# grbl2prll.net
KiCad netlist of a schematic drawn in EAGLE
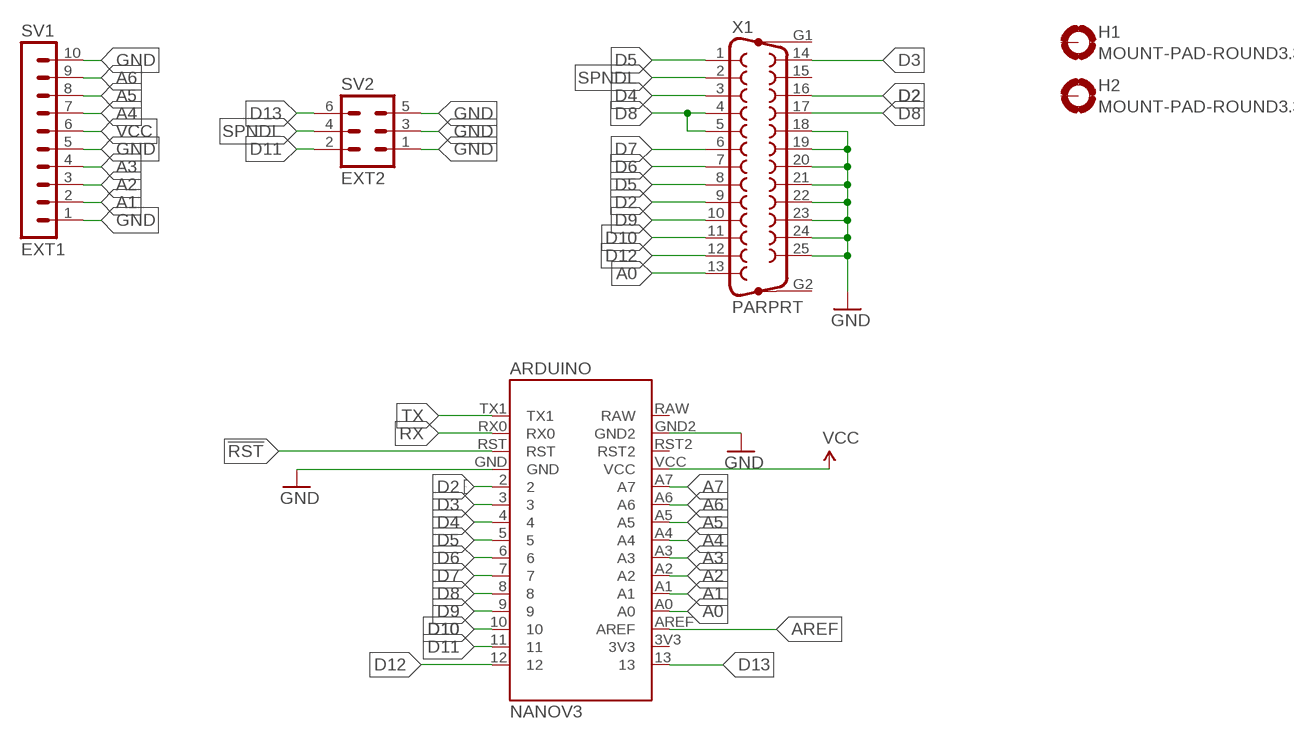
[diagram p0: schematic, sheet 1]

(export (version "E")
  (design (tool "Eeschema 10.0.6"))
  (components
    (comp (ref "ARDUINO")
      (value "NANOV3")
      (footprint "eagle-import:NANOV3")
      (libsource (lib "eagle-import") (part "NANOV3"))
    )
    (comp (ref "H1")
      (value "MOUNT-PAD-ROUND3.3")
      (footprint "eagle-import:3,3-PAD")
      (libsource (lib "eagle-import") (part "MOUNT-PAD-ROUND3.3"))
    )
    (comp (ref "H2")
      (value "MOUNT-PAD-ROUND3.3")
      (footprint "eagle-import:3,3-PAD")
      (libsource (lib "eagle-import") (part "MOUNT-PAD-ROUND3.3"))
    )
    (comp (ref "SV1")
      (value "EXT1")
      (footprint "eagle-import:MA10-1")
      (libsource (lib "eagle-import") (part "MA10-1"))
    )
    (comp (ref "SV2")
      (value "EXT2")
      (footprint "eagle-import:MA03-2")
      (libsource (lib "eagle-import") (part "MA03-2"))
    )
    (comp (ref "X1")
      (value "PARPRT")
      (footprint "eagle-import:F25HP")
      (libsource (lib "eagle-import") (part "F25HP"))
    )
  )
  (nets
    (net (code "1") (name "/~{RST}") (class "Default")
      (node (ref "ARDUINO") (pin "RST") (pinfunction "RST_RST") (pintype "bidirectional"))
    )
    (net (code "2") (name "A0") (class "Default")
      (node (ref "ARDUINO") (pin "A0") (pinfunction "A0_A0") (pintype "bidirectional"))
      (node (ref "X1") (pin "13") (pinfunction "13_13") (pintype "passive"))
    )
    (net (code "3") (name "A1") (class "Default")
      (node (ref "ARDUINO") (pin "A1") (pinfunction "A1_A1") (pintype "bidirectional"))
      (node (ref "SV1") (pin "2") (pinfunction "2_2") (pintype "passive"))
    )
    (net (code "4") (name "A2") (class "Default")
      (node (ref "ARDUINO") (pin "A2") (pinfunction "A2_A2") (pintype "bidirectional"))
      (node (ref "SV1") (pin "3") (pinfunction "3_3") (pintype "passive"))
    )
    (net (code "5") (name "A3") (class "Default")
      (node (ref "ARDUINO") (pin "A3") (pinfunction "A3_A3") (pintype "bidirectional"))
      (node (ref "SV1") (pin "4") (pinfunction "4_4") (pintype "passive"))
    )
    (net (code "6") (name "A4") (class "Default")
      (node (ref "ARDUINO") (pin "A4") (pinfunction "A4_A4") (pintype "bidirectional"))
      (node (ref "SV1") (pin "7") (pinfunction "7_7") (pintype "passive"))
    )
    (net (code "7") (name "A5") (class "Default")
      (node (ref "ARDUINO") (pin "A5") (pinfunction "A5_A5") (pintype "bidirectional"))
      (node (ref "SV1") (pin "8") (pinfunction "8_8") (pintype "passive"))
    )
    (net (code "8") (name "A6") (class "Default")
      (node (ref "ARDUINO") (pin "A6") (pinfunction "A6_A6") (pintype "bidirectional"))
      (node (ref "SV1") (pin "9") (pinfunction "9_9") (pintype "passive"))
    )
    (net (code "9") (name "A7") (class "Default")
      (node (ref "ARDUINO") (pin "A7") (pinfunction "A7_A7") (pintype "bidirectional"))
    )
    (net (code "10") (name "AREF") (class "Default")
      (node (ref "ARDUINO") (pin "AREF") (pinfunction "AREF_AREF") (pintype "bidirectional"))
    )
    (net (code "11") (name "D2") (class "Default")
      (node (ref "ARDUINO") (pin "2") (pinfunction "2_2") (pintype "bidirectional"))
      (node (ref "X1") (pin "16") (pinfunction "16_16") (pintype "passive"))
      (node (ref "X1") (pin "9") (pinfunction "9_9") (pintype "passive"))
    )
    (net (code "12") (name "D3") (class "Default")
      (node (ref "ARDUINO") (pin "3") (pinfunction "3_3") (pintype "bidirectional"))
      (node (ref "X1") (pin "14") (pinfunction "14_14") (pintype "passive"))
    )
    (net (code "13") (name "D4") (class "Default")
      (node (ref "ARDUINO") (pin "4") (pinfunction "4_4") (pintype "bidirectional"))
      (node (ref "X1") (pin "3") (pinfunction "3_3") (pintype "passive"))
    )
    (net (code "14") (name "D5") (class "Default")
      (node (ref "ARDUINO") (pin "5") (pinfunction "5_5") (pintype "bidirectional"))
      (node (ref "X1") (pin "1") (pinfunction "1_1") (pintype "passive"))
      (node (ref "X1") (pin "8") (pinfunction "8_8") (pintype "passive"))
    )
    (net (code "15") (name "D6") (class "Default")
      (node (ref "ARDUINO") (pin "6") (pinfunction "6_6") (pintype "bidirectional"))
      (node (ref "X1") (pin "7") (pinfunction "7_7") (pintype "passive"))
    )
    (net (code "16") (name "D7") (class "Default")
      (node (ref "ARDUINO") (pin "7") (pinfunction "7_7") (pintype "bidirectional"))
      (node (ref "X1") (pin "6") (pinfunction "6_6") (pintype "passive"))
    )
    (net (code "17") (name "D8") (class "Default")
      (node (ref "ARDUINO") (pin "8") (pinfunction "8_8") (pintype "bidirectional"))
      (node (ref "X1") (pin "17") (pinfunction "17_17") (pintype "passive"))
      (node (ref "X1") (pin "4") (pinfunction "4_4") (pintype "passive"))
      (node (ref "X1") (pin "5") (pinfunction "5_5") (pintype "passive"))
    )
    (net (code "18") (name "D9") (class "Default")
      (node (ref "ARDUINO") (pin "9") (pinfunction "9_9") (pintype "bidirectional"))
      (node (ref "X1") (pin "10") (pinfunction "10_10") (pintype "passive"))
    )
    (net (code "19") (name "D10") (class "Default")
      (node (ref "ARDUINO") (pin "10") (pinfunction "10_10") (pintype "bidirectional"))
      (node (ref "X1") (pin "11") (pinfunction "11_11") (pintype "passive"))
    )
    (net (code "20") (name "D11") (class "Default")
      (node (ref "ARDUINO") (pin "11") (pinfunction "11_11") (pintype "bidirectional"))
      (node (ref "SV2") (pin "2") (pinfunction "2_2") (pintype "passive"))
    )
    (net (code "21") (name "D12") (class "Default")
      (node (ref "ARDUINO") (pin "12") (pinfunction "12_12") (pintype "bidirectional"))
      (node (ref "X1") (pin "12") (pinfunction "12_12") (pintype "passive"))
    )
    (net (code "22") (name "D13") (class "Default")
      (node (ref "ARDUINO") (pin "13") (pinfunction "13_13") (pintype "bidirectional"))
      (node (ref "SV2") (pin "6") (pinfunction "6_6") (pintype "passive"))
    )
    (net (code "23") (name "GND") (class "Default")
      (node (ref "ARDUINO") (pin "GND") (pinfunction "GND_GND") (pintype "bidirectional"))
      (node (ref "ARDUINO") (pin "GND2") (pinfunction "GND2_GND2") (pintype "bidirectional"))
      (node (ref "SV1") (pin "1") (pinfunction "1_1") (pintype "passive"))
      (node (ref "SV1") (pin "10") (pinfunction "10_10") (pintype "passive"))
      (node (ref "SV1") (pin "5") (pinfunction "5_5") (pintype "passive"))
      (node (ref "SV2") (pin "1") (pinfunction "1_1") (pintype "passive"))
      (node (ref "SV2") (pin "3") (pinfunction "3_3") (pintype "passive"))
      (node (ref "SV2") (pin "5") (pinfunction "5_5") (pintype "passive"))
      (node (ref "X1") (pin "18") (pinfunction "18_18") (pintype "passive"))
      (node (ref "X1") (pin "19") (pinfunction "19_19") (pintype "passive"))
      (node (ref "X1") (pin "20") (pinfunction "20_20") (pintype "passive"))
      (node (ref "X1") (pin "21") (pinfunction "21_21") (pintype "passive"))
      (node (ref "X1") (pin "22") (pinfunction "22_22") (pintype "passive"))
      (node (ref "X1") (pin "23") (pinfunction "23_23") (pintype "passive"))
      (node (ref "X1") (pin "24") (pinfunction "24_24") (pintype "passive"))
      (node (ref "X1") (pin "25") (pinfunction "25_25") (pintype "passive"))
    )
    (net (code "24") (name "RX") (class "Default")
      (node (ref "ARDUINO") (pin "RX0") (pinfunction "RX0_RX0") (pintype "bidirectional"))
    )
    (net (code "25") (name "SPNDL") (class "Default")
      (node (ref "SV2") (pin "4") (pinfunction "4_4") (pintype "passive"))
      (node (ref "X1") (pin "2") (pinfunction "2_2") (pintype "passive"))
    )
    (net (code "26") (name "TX") (class "Default")
      (node (ref "ARDUINO") (pin "TX1") (pinfunction "TX1_TX1") (pintype "bidirectional"))
    )
    (net (code "27") (name "VCC") (class "Default")
      (node (ref "ARDUINO") (pin "VCC") (pinfunction "VCC_VCC") (pintype "bidirectional"))
      (node (ref "SV1") (pin "6") (pinfunction "6_6") (pintype "passive"))
    )
    (net (code "28") (name "unconnected-(ARDUINO-Pad3V3)") (class "Default")
      (node (ref "ARDUINO") (pin "3V3") (pinfunction "3V3_3V3") (pintype "bidirectional"))
    )
    (net (code "29") (name "unconnected-(ARDUINO-PadRAW)") (class "Default")
      (node (ref "ARDUINO") (pin "RAW") (pinfunction "RAW_RAW") (pintype "bidirectional"))
    )
    (net (code "30") (name "unconnected-(ARDUINO-PadRST2)") (class "Default")
      (node (ref "ARDUINO") (pin "RST2") (pinfunction "RST2_RST2") (pintype "bidirectional"))
    )
    (net (code "31") (name "unconnected-(H1-MOUNT-PadB3,3)") (class "Default")
      (node (ref "H1") (pin "B3,3") (pinfunction "MOUNT_B3,3") (pintype "passive"))
    )
    (net (code "32") (name "unconnected-(H2-MOUNT-PadB3,3)") (class "Default")
      (node (ref "H2") (pin "B3,3") (pinfunction "MOUNT_B3,3") (pintype "passive"))
    )
    (net (code "33") (name "unconnected-(X1-Pad15)") (class "Default")
      (node (ref "X1") (pin "15") (pinfunction "15_15") (pintype "passive"))
    )
    (net (code "34") (name "unconnected-(X1-PadG1)") (class "Default")
      (node (ref "X1") (pin "G1") (pinfunction "G1_G1") (pintype "passive"))
    )
    (net (code "35") (name "unconnected-(X1-PadG2)") (class "Default")
      (node (ref "X1") (pin "G2") (pinfunction "G2_G2") (pintype "passive"))
    )
  )
)
